# 4_motor.net
KiCad netlist of a schematic drawn in Altium Designer
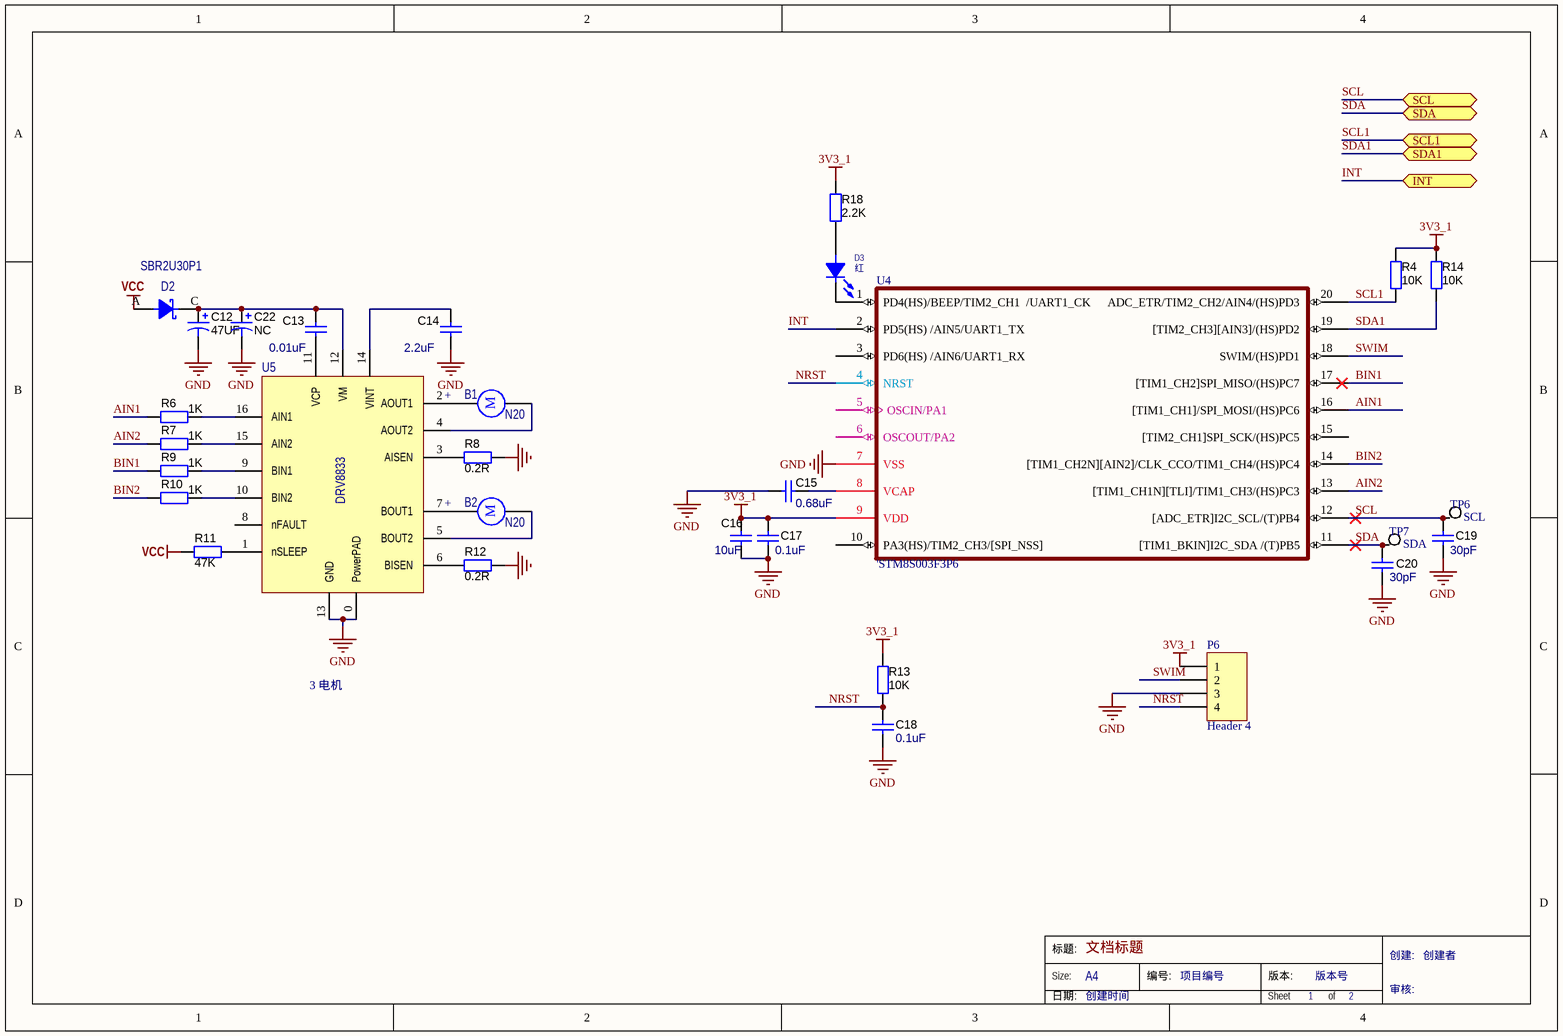
[diagram p0: 4.motor.SchDoc]

(export (version "E")
  (design (tool "Eeschema 10.0.6"))
  (components
    (comp (ref "B1")
      (value "N20")
      (footprint "2PIN/2.54MM座子")
      (description "Motor, General Kind")
      (fields (field (name "PUBLISHER") "Altium Limited"))
      (libsource (lib "Miscellaneous Devices") (part "Motor"))
    )
    (comp (ref "B2")
      (value "N20")
      (footprint "2PIN/2.54MM座子")
      (description "Motor, General Kind")
      (fields (field (name "PUBLISHER") "Altium Limited"))
      (libsource (lib "Miscellaneous Devices") (part "Motor"))
    )
    (comp (ref "C12")
      (value "47UF")
      (footprint "0805")
      (description "CAP ALUM 22UF 10V 20% SMD")
      (fields
        (field (name "PARTNUMBER") "EEE-1AA220WR")
        (field (name "MANUFACTURER") "Panasonic - ECG")
        (field (name "PUBLISHER") "National Semiconductor")
      )
      (libsource (lib "03.常用器件") (part "CAP3_pol"))
    )
    (comp (ref "C13")
      (value "0.01uF")
      (footprint "0402")
      (description "CAP, CERM, 0.01uF, 100V, +/-5%, X7R, 0603")
      (fields (field (name "PARTNUMBER") "06031C103JAT2A") (field (name "MANUFACTURER") "AVX"))
      (libsource (lib "03.常用器件") (part "CAP1_npol"))
    )
    (comp (ref "C14")
      (value "2.2uF")
      (footprint "0402")
      (description "CAP, CERM, 0.01uF, 100V, +/-5%, X7R, 0603")
      (fields (field (name "PARTNUMBER") "06031C103JAT2A") (field (name "MANUFACTURER") "AVX"))
      (libsource (lib "03.常用器件") (part "CAP1_npol"))
    )
    (comp (ref "C15")
      (value "0.68uF")
      (footprint "0402")
      (description "CAP, CERM, 0.01uF, 100V, +/-5%, X7R, 0603")
      (fields (field (name "PARTNUMBER") "06031C103JAT2A") (field (name "MANUFACTURER") "AVX"))
      (libsource (lib "03.常用器件") (part "CAP1_npol"))
    )
    (comp (ref "C16")
      (value "10uF")
      (footprint "0603")
      (description "CAP, CERM, 0.01uF, 100V, +/-5%, X7R, 0603")
      (fields (field (name "PARTNUMBER") "06031C103JAT2A") (field (name "MANUFACTURER") "AVX"))
      (libsource (lib "03.常用器件") (part "CAP1_npol"))
    )
    (comp (ref "C17")
      (value "0.1uF")
      (footprint "0402")
      (description "CAP, CERM, 0.01uF, 100V, +/-5%, X7R, 0603")
      (fields (field (name "PARTNUMBER") "06031C103JAT2A") (field (name "MANUFACTURER") "AVX"))
      (libsource (lib "03.常用器件") (part "CAP1_npol"))
    )
    (comp (ref "C18")
      (value "0.1uF")
      (footprint "0402")
      (description "CAP, CERM, 0.01uF, 100V, +/-5%, X7R, 0603")
      (fields (field (name "PARTNUMBER") "06031C103JAT2A") (field (name "MANUFACTURER") "AVX"))
      (libsource (lib "03.常用器件") (part "CAP1_npol"))
    )
    (comp (ref "C19")
      (value "30pF")
      (footprint "0402")
      (description "CAP, CERM, 0.01uF, 100V, +/-5%, X7R, 0603")
      (fields (field (name "PARTNUMBER") "06031C103JAT2A") (field (name "MANUFACTURER") "AVX"))
      (libsource (lib "03.常用器件") (part "CAP1_npol"))
    )
    (comp (ref "C20")
      (value "30pF")
      (footprint "0402")
      (description "CAP, CERM, 0.01uF, 100V, +/-5%, X7R, 0603")
      (fields (field (name "PARTNUMBER") "06031C103JAT2A") (field (name "MANUFACTURER") "AVX"))
      (libsource (lib "03.常用器件") (part "CAP1_npol"))
    )
    (comp (ref "C22")
      (value "NC")
      (footprint "0805")
      (description "CAP ALUM 22UF 10V 20% SMD")
      (fields
        (field (name "PARTNUMBER") "EEE-1AA220WR")
        (field (name "MANUFACTURER") "Panasonic - ECG")
        (field (name "PUBLISHER") "National Semiconductor")
      )
      (libsource (lib "03.常用器件") (part "CAP3_pol"))
    )
    (comp (ref "D2")
      (value "SBR2U30P1")
      (footprint "POWERDI123")
      (fields (field (name "PARTNUMBER") "?") (field (name "PUBLISHER") "Altium Limited"))
      (libsource (lib "03.常用器件") (part "Diode_Schottky"))
    )
    (comp (ref "D3")
      (value "红")
      (footprint "0603LED")
      (fields (field (name "MANUFACTURER") "?"))
      (libsource (lib "03.常用器件") (part "LED1"))
    )
    (comp (ref "P6")
      (value "Header 4")
      (footprint "排针2.54MM/4PIN")
      (description "Header, 4-Pin")
      (fields (field (name "PUBLISHER") "Altium Limited"))
      (libsource (lib "Miscellaneous Connectors") (part "Header 4"))
    )
    (comp (ref "R4")
      (value "10K")
      (footprint "0402")
      (description "RES, 1.0k ohm, 5%, 0.1W, 0603")
      (fields
        (field (name "PARTNUMBER") "RC0603JR-071KL")
        (field (name "MANUFACTURER") "Yageo America")
        (field (name "PUBLISHER") "Texas Instruments")
      )
      (libsource (lib "03.常用器件") (part "RES1"))
    )
    (comp (ref "R6")
      (value "1K")
      (footprint "0402")
      (description "RES, 1.0k ohm, 5%, 0.1W, 0603")
      (fields
        (field (name "PARTNUMBER") "RC0603JR-071KL")
        (field (name "MANUFACTURER") "Yageo America")
        (field (name "PUBLISHER") "Texas Instruments")
      )
      (libsource (lib "") (part "RES1_1"))
    )
    (comp (ref "R7")
      (value "1K")
      (footprint "0402")
      (description "RES, 1.0k ohm, 5%, 0.1W, 0603")
      (fields
        (field (name "PARTNUMBER") "RC0603JR-071KL")
        (field (name "MANUFACTURER") "Yageo America")
        (field (name "PUBLISHER") "Texas Instruments")
      )
      (libsource (lib "") (part "RES1_1"))
    )
    (comp (ref "R8")
      (value "0.2R")
      (footprint "0603")
      (description "RES, 1.0k ohm, 5%, 0.1W, 0603")
      (fields
        (field (name "PARTNUMBER") "RC0603JR-071KL")
        (field (name "MANUFACTURER") "Yageo America")
        (field (name "PUBLISHER") "Texas Instruments")
      )
      (libsource (lib "") (part "RES1_1"))
    )
    (comp (ref "R9")
      (value "1K")
      (footprint "0402")
      (description "RES, 1.0k ohm, 5%, 0.1W, 0603")
      (fields
        (field (name "PARTNUMBER") "RC0603JR-071KL")
        (field (name "MANUFACTURER") "Yageo America")
        (field (name "PUBLISHER") "Texas Instruments")
      )
      (libsource (lib "") (part "RES1_1"))
    )
    (comp (ref "R10")
      (value "1K")
      (footprint "0402")
      (description "RES, 1.0k ohm, 5%, 0.1W, 0603")
      (fields
        (field (name "PARTNUMBER") "RC0603JR-071KL")
        (field (name "MANUFACTURER") "Yageo America")
        (field (name "PUBLISHER") "Texas Instruments")
      )
      (libsource (lib "") (part "RES1_1"))
    )
    (comp (ref "R11")
      (value "47K")
      (footprint "0402")
      (description "RES, 1.0k ohm, 5%, 0.1W, 0603")
      (fields
        (field (name "PARTNUMBER") "RC0603JR-071KL")
        (field (name "MANUFACTURER") "Yageo America")
        (field (name "PUBLISHER") "Texas Instruments")
      )
      (libsource (lib "") (part "RES1_1"))
    )
    (comp (ref "R12")
      (value "0.2R")
      (footprint "0603")
      (description "RES, 1.0k ohm, 5%, 0.1W, 0603")
      (fields
        (field (name "PARTNUMBER") "RC0603JR-071KL")
        (field (name "MANUFACTURER") "Yageo America")
        (field (name "PUBLISHER") "Texas Instruments")
      )
      (libsource (lib "") (part "RES1_1"))
    )
    (comp (ref "R13")
      (value "10K")
      (footprint "0402")
      (description "RES, 1.0k ohm, 5%, 0.1W, 0603")
      (fields
        (field (name "PARTNUMBER") "RC0603JR-071KL")
        (field (name "MANUFACTURER") "Yageo America")
        (field (name "PUBLISHER") "Texas Instruments")
      )
      (libsource (lib "") (part "RES1_2"))
    )
    (comp (ref "R14")
      (value "10K")
      (footprint "0402")
      (description "RES, 1.0k ohm, 5%, 0.1W, 0603")
      (fields
        (field (name "PARTNUMBER") "RC0603JR-071KL")
        (field (name "MANUFACTURER") "Yageo America")
        (field (name "PUBLISHER") "Texas Instruments")
      )
      (libsource (lib "03.常用器件") (part "RES1"))
    )
    (comp (ref "R18")
      (value "2.2K")
      (footprint "0402")
      (description "RES, 1.0k ohm, 5%, 0.1W, 0603")
      (fields
        (field (name "PARTNUMBER") "RC0603JR-071KL")
        (field (name "MANUFACTURER") "Yageo America")
        (field (name "PUBLISHER") "Texas Instruments")
      )
      (libsource (lib "") (part "RES1_2"))
    )
    (comp (ref "TP6")
      (value "SCL")
      (footprint "测试点")
      (description "Test Point")
      (libsource (lib "my_Schlib") (part "TP"))
    )
    (comp (ref "TP7")
      (value "SDA")
      (footprint "测试点")
      (description "Test Point")
      (libsource (lib "my_Schlib") (part "TP"))
    )
    (comp (ref "U4")
      (value "'STM8S003F3P6")
      (footprint "UFQFPN20")
      (description "ST 8-bit  Microcontroller")
      (libsource (lib "Microcontroller Unit") (part "STM8S103F2P6"))
    )
    (comp (ref "U5")
      (value "DRV8833")
      (footprint "HTSSOP -16(PWP)")
      (description "DUAL H-BRIDGE MOTOR DRIVER")
      (libsource (lib "DRV8833") (part "DRV8833PWP"))
    )
  )
  (nets
    (net (code "1") (name "/AIN1") (class "Default")
      (node (ref "R6") (pin "1") (pinfunction "1_1") (pintype "passive"))
      (node (ref "U4") (pin "16") (pinfunction "[TIM1_CH1]/SPI_MOSI/(HS)PC6_16") (pintype "bidirectional"))
    )
    (net (code "2") (name "/AIN2") (class "Default")
      (node (ref "R7") (pin "1") (pinfunction "1_1") (pintype "passive"))
      (node (ref "U4") (pin "13") (pinfunction "[TIM1_CH1N][TLI]/TIM1_CH3/(HS)PC3_13") (pintype "bidirectional"))
    )
    (net (code "3") (name "/BIN1") (class "Default")
      (node (ref "R9") (pin "1") (pinfunction "1_1") (pintype "passive"))
      (node (ref "U4") (pin "17") (pinfunction "[TIM1_CH2]SPI_MISO/(HS)PC7_17") (pintype "bidirectional"))
    )
    (net (code "4") (name "/BIN2") (class "Default")
      (node (ref "R10") (pin "1") (pinfunction "1_1") (pintype "passive"))
      (node (ref "U4") (pin "14") (pinfunction "[TIM1_CH2N][AIN2]/CLK_CCO/TIM1_CH4/(HS)PC4_14") (pintype "bidirectional"))
    )
    (net (code "5") (name "/INT") (class "Default")
      (node (ref "U4") (pin "2") (pinfunction "PD5(HS)_/AIN5/UART1_TX_2") (pintype "bidirectional"))
    )
    (net (code "6") (name "/NRST") (class "Default")
      (node (ref "C18") (pin "2") (pinfunction "2_2") (pintype "passive"))
      (node (ref "P6") (pin "4") (pinfunction "4_4") (pintype "passive"))
      (node (ref "R13") (pin "2") (pinfunction "2_2") (pintype "passive"))
      (node (ref "U4") (pin "4") (pinfunction "NRST_4") (pintype "bidirectional"))
    )
    (net (code "8") (name "/SCL1") (class "Default")
      (node (ref "R4") (pin "1") (pinfunction "1_1") (pintype "passive"))
      (node (ref "U4") (pin "20") (pinfunction "ADC_ETR/TIM2_CH2/AIN4/(HS)PD3_20") (pintype "bidirectional"))
    )
    (net (code "10") (name "/SDA1") (class "Default")
      (node (ref "R14") (pin "1") (pinfunction "1_1") (pintype "passive"))
      (node (ref "U4") (pin "19") (pinfunction "[TIM2_CH3][AIN3]/(HS)PD2_19") (pintype "bidirectional"))
    )
    (net (code "11") (name "/SWIM") (class "Default")
      (node (ref "P6") (pin "2") (pinfunction "2_2") (pintype "passive"))
      (node (ref "U4") (pin "18") (pinfunction "SWIM/(HS)PD1_18") (pintype "bidirectional"))
    )
    (net (code "12") (name "3V3_1") (class "Default")
      (node (ref "C16") (pin "1") (pinfunction "1_1") (pintype "passive"))
      (node (ref "C17") (pin "2") (pinfunction "2_2") (pintype "passive"))
      (node (ref "P6") (pin "1") (pinfunction "1_1") (pintype "passive"))
      (node (ref "R13") (pin "1") (pinfunction "1_1") (pintype "passive"))
      (node (ref "R14") (pin "2") (pinfunction "2_2") (pintype "passive"))
      (node (ref "R18") (pin "1") (pinfunction "1_1") (pintype "passive"))
      (node (ref "R4") (pin "2") (pinfunction "2_2") (pintype "passive"))
      (node (ref "U4") (pin "9") (pinfunction "VDD_9") (pintype "power_in"))
    )
    (net (code "13") (name "GND") (class "Default")
      (node (ref "C12") (pin "2") (pinfunction "-_2") (pintype "passive"))
      (node (ref "C14") (pin "1") (pinfunction "1_1") (pintype "passive"))
      (node (ref "C15") (pin "2") (pinfunction "2_2") (pintype "passive"))
      (node (ref "C16") (pin "2") (pinfunction "2_2") (pintype "passive"))
      (node (ref "C17") (pin "1") (pinfunction "1_1") (pintype "passive"))
      (node (ref "C18") (pin "1") (pinfunction "1_1") (pintype "passive"))
      (node (ref "C19") (pin "1") (pinfunction "1_1") (pintype "passive"))
      (node (ref "C20") (pin "1") (pinfunction "1_1") (pintype "passive"))
      (node (ref "C22") (pin "2") (pinfunction "-_2") (pintype "passive"))
      (node (ref "P6") (pin "3") (pinfunction "3_3") (pintype "passive"))
      (node (ref "R12") (pin "2") (pinfunction "2_2") (pintype "passive"))
      (node (ref "R8") (pin "2") (pinfunction "2_2") (pintype "passive"))
      (node (ref "U4") (pin "7") (pinfunction "VSS_7") (pintype "power_in"))
      (node (ref "U5") (pin "0") (pinfunction "PowerPAD_0") (pintype "passive"))
      (node (ref "U5") (pin "13") (pinfunction "GND_13") (pintype "passive"))
    )
    (net (code "14") (name "Net-(C12-+)") (class "Default")
      (node (ref "C12") (pin "1") (pinfunction "+_1") (pintype "passive"))
      (node (ref "C13") (pin "2") (pinfunction "2_2") (pintype "passive"))
      (node (ref "C22") (pin "1") (pinfunction "+_1") (pintype "passive"))
      (node (ref "D2") (pin "C") (pinfunction "CATHODE_C") (pintype "passive"))
      (node (ref "U5") (pin "12") (pinfunction "VM_12") (pintype "passive"))
    )
    (net (code "15") (name "Net-(D3-ANODE)") (class "Default")
      (node (ref "D3") (pin "A") (pinfunction "ANODE_A") (pintype "passive"))
      (node (ref "R18") (pin "2") (pinfunction "2_2") (pintype "passive"))
    )
    (net (code "16") (name "Net-(D3-CATHODE)") (class "Default")
      (node (ref "D3") (pin "C") (pinfunction "CATHODE_C") (pintype "passive"))
      (node (ref "U4") (pin "1") (pinfunction "PD4(HS)/BEEP/TIM2_CH1__/UART1_CK_1") (pintype "bidirectional"))
    )
    (net (code "17") (name "Net-(U4-VCAP)") (class "Default")
      (node (ref "C15") (pin "1") (pinfunction "1_1") (pintype "passive"))
      (node (ref "U4") (pin "8") (pinfunction "VCAP_8") (pintype "power_in"))
    )
    (net (code "18") (name "Net-(U4-[ADC_ETR]I2C_SCL{slash}(T)PB4)") (class "Default")
      (node (ref "C19") (pin "2") (pinfunction "2_2") (pintype "passive"))
      (node (ref "TP6") (pin "1") (pinfunction "1_1") (pintype "passive"))
      (node (ref "U4") (pin "12") (pinfunction "[ADC_ETR]I2C_SCL/(T)PB4_12") (pintype "bidirectional"))
    )
    (net (code "19") (name "Net-(U4-[TIM1_BKIN]I2C_SDA_{slash}(T)PB5)") (class "Default")
      (node (ref "C20") (pin "2") (pinfunction "2_2") (pintype "passive"))
      (node (ref "TP7") (pin "1") (pinfunction "1_1") (pintype "passive"))
      (node (ref "U4") (pin "11") (pinfunction "[TIM1_BKIN]I2C_SDA_/(T)PB5_11") (pintype "bidirectional"))
    )
    (net (code "20") (name "Net-(U5-AIN1)") (class "Default")
      (node (ref "R6") (pin "2") (pinfunction "2_2") (pintype "passive"))
      (node (ref "U5") (pin "16") (pinfunction "AIN1_16") (pintype "passive"))
    )
    (net (code "21") (name "Net-(U5-AIN2)") (class "Default")
      (node (ref "R7") (pin "2") (pinfunction "2_2") (pintype "passive"))
      (node (ref "U5") (pin "15") (pinfunction "AIN2_15") (pintype "passive"))
    )
    (net (code "22") (name "Net-(U5-AISEN)") (class "Default")
      (node (ref "R8") (pin "1") (pinfunction "1_1") (pintype "passive"))
      (node (ref "U5") (pin "3") (pinfunction "AISEN_3") (pintype "passive"))
    )
    (net (code "23") (name "Net-(U5-AOUT1)") (class "Default")
      (node (ref "B1") (pin "1") (pinfunction "1_1") (pintype "passive"))
      (node (ref "U5") (pin "2") (pinfunction "AOUT1_2") (pintype "passive"))
    )
    (net (code "24") (name "Net-(U5-AOUT2)") (class "Default")
      (node (ref "B1") (pin "2") (pinfunction "2_2") (pintype "passive"))
      (node (ref "U5") (pin "4") (pinfunction "AOUT2_4") (pintype "passive"))
    )
    (net (code "25") (name "Net-(U5-BIN1)") (class "Default")
      (node (ref "R9") (pin "2") (pinfunction "2_2") (pintype "passive"))
      (node (ref "U5") (pin "9") (pinfunction "BIN1_9") (pintype "passive"))
    )
    (net (code "26") (name "Net-(U5-BIN2)") (class "Default")
      (node (ref "R10") (pin "2") (pinfunction "2_2") (pintype "passive"))
      (node (ref "U5") (pin "10") (pinfunction "BIN2_10") (pintype "passive"))
    )
    (net (code "27") (name "Net-(U5-BISEN)") (class "Default")
      (node (ref "R12") (pin "1") (pinfunction "1_1") (pintype "passive"))
      (node (ref "U5") (pin "6") (pinfunction "BISEN_6") (pintype "passive"))
    )
    (net (code "28") (name "Net-(U5-BOUT1)") (class "Default")
      (node (ref "B2") (pin "1") (pinfunction "1_1") (pintype "passive"))
      (node (ref "U5") (pin "7") (pinfunction "BOUT1_7") (pintype "passive"))
    )
    (net (code "29") (name "Net-(U5-BOUT2)") (class "Default")
      (node (ref "B2") (pin "2") (pinfunction "2_2") (pintype "passive"))
      (node (ref "U5") (pin "5") (pinfunction "BOUT2_5") (pintype "passive"))
    )
    (net (code "30") (name "Net-(U5-VCP)") (class "Default")
      (node (ref "C13") (pin "1") (pinfunction "1_1") (pintype "passive"))
      (node (ref "U5") (pin "11") (pinfunction "VCP_11") (pintype "passive"))
    )
    (net (code "31") (name "Net-(U5-VINT)") (class "Default")
      (node (ref "C14") (pin "2") (pinfunction "2_2") (pintype "passive"))
      (node (ref "U5") (pin "14") (pinfunction "VINT_14") (pintype "passive"))
    )
    (net (code "32") (name "Net-(U5-nSLEEP)") (class "Default")
      (node (ref "R11") (pin "2") (pinfunction "2_2") (pintype "passive"))
      (node (ref "U5") (pin "1") (pinfunction "nSLEEP_1") (pintype "passive"))
    )
    (net (code "33") (name "VCC") (class "Default")
      (node (ref "D2") (pin "A") (pinfunction "ANODE_A") (pintype "passive"))
      (node (ref "R11") (pin "1") (pinfunction "1_1") (pintype "passive"))
    )
    (net (code "34") (name "unconnected-(U4-OSCIN{slash}PA1-Pad5)") (class "Default")
      (node (ref "U4") (pin "5") (pinfunction "OSCIN/PA1_5") (pintype "bidirectional"))
    )
    (net (code "35") (name "unconnected-(U4-OSCOUT{slash}PA2-Pad6)") (class "Default")
      (node (ref "U4") (pin "6") (pinfunction "OSCOUT/PA2_6") (pintype "bidirectional"))
    )
    (net (code "36") (name "unconnected-(U4-PA3(HS){slash}TIM2_CH3{slash}[SPI_NSS]-Pad10)") (class "Default")
      (node (ref "U4") (pin "10") (pinfunction "PA3(HS)/TIM2_CH3/[SPI_NSS]_10") (pintype "bidirectional"))
    )
    (net (code "37") (name "unconnected-(U4-PD6(HS)_{slash}AIN6{slash}UART1_RX-Pad3)") (class "Default")
      (node (ref "U4") (pin "3") (pinfunction "PD6(HS)_/AIN6/UART1_RX_3") (pintype "bidirectional"))
    )
    (net (code "38") (name "unconnected-(U4-[TIM2_CH1]SPI_SCK{slash}(HS)PC5-Pad15)") (class "Default")
      (node (ref "U4") (pin "15") (pinfunction "[TIM2_CH1]SPI_SCK/(HS)PC5_15") (pintype "bidirectional"))
    )
    (net (code "39") (name "unconnected-(U5-nFAULT-Pad8)") (class "Default")
      (node (ref "U5") (pin "8") (pinfunction "nFAULT_8") (pintype "passive"))
    )
  )
)
